# Sensor_Board_0x04_Luminosity_TSL2561_v1.net
KiCad netlist of a schematic drawn in EAGLE
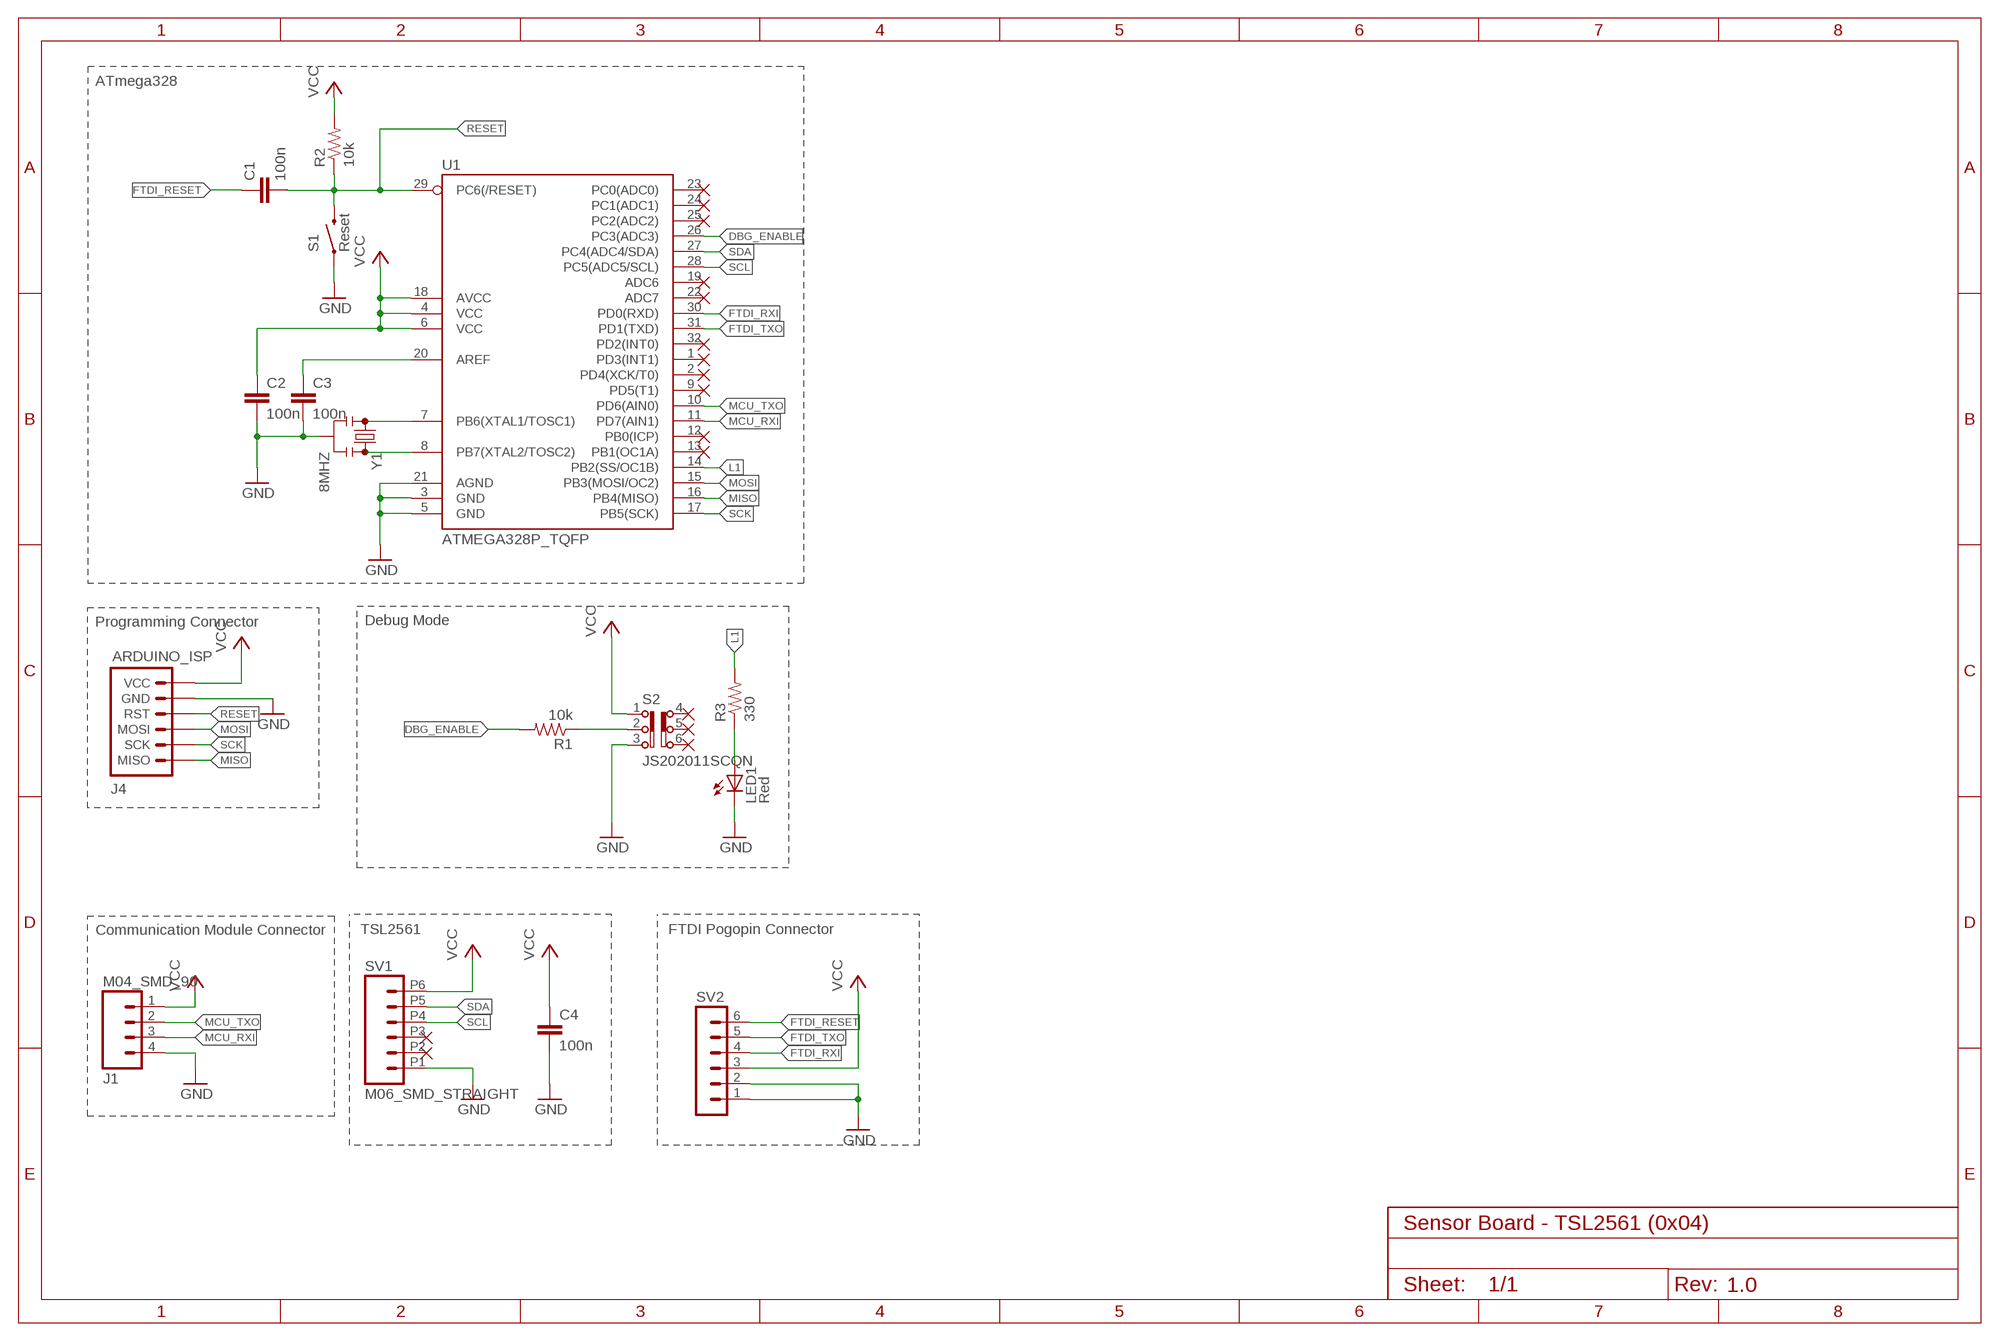
[diagram p0: schematic, sheet 1]

(export (version "E")
  (design (tool "Eeschema 10.0.6"))
  (components
    (comp (ref "C1")
      (value "100n")
      (footprint "eagle-import:C0805")
      (libsource (lib "eagle-import") (part "C"))
    )
    (comp (ref "C2")
      (value "100n")
      (footprint "eagle-import:C0805")
      (libsource (lib "eagle-import") (part "C"))
    )
    (comp (ref "C3")
      (value "100n")
      (footprint "eagle-import:C0805")
      (libsource (lib "eagle-import") (part "C"))
    )
    (comp (ref "C4")
      (value "100n")
      (footprint "eagle-import:C0805")
      (libsource (lib "eagle-import") (part "C"))
    )
    (comp (ref "J1")
      (value "M04_SMD_90")
      (footprint "eagle-import:M04_SMD_90")
      (libsource (lib "eagle-import") (part "M04_SMD_90"))
    )
    (comp (ref "J4")
      (value "ARDUINO_ISP")
      (footprint "eagle-import:M-2X3")
      (libsource (lib "eagle-import") (part "ARDUINO_ISP"))
    )
    (comp (ref "LED1")
      (value "Red")
      (footprint "eagle-import:SML0805")
      (libsource (lib "eagle-import") (part "LEDSML0805"))
    )
    (comp (ref "R1")
      (value "10k")
      (footprint "eagle-import:0805")
      (libsource (lib "eagle-import") (part "RESISTOR0805-RES"))
    )
    (comp (ref "R2")
      (value "10k")
      (footprint "eagle-import:0805")
      (libsource (lib "eagle-import") (part "RESISTOR0805-RES"))
    )
    (comp (ref "R3")
      (value "330")
      (footprint "eagle-import:0805")
      (libsource (lib "eagle-import") (part "RESISTOR0805-RES"))
    )
    (comp (ref "S1")
      (value "Reset")
      (footprint "eagle-import:M-PUSHBUTTON-SMD")
      (libsource (lib "eagle-import") (part "PUSHBUTTON"))
    )
    (comp (ref "S2")
      (value "JS202011SCQN")
      (footprint "eagle-import:JS202011SCQN")
      (libsource (lib "eagle-import") (part "JS202011SCQN"))
    )
    (comp (ref "SV1")
      (value "M06_SMD_STRAIGHT")
      (footprint "eagle-import:M06_SMD_STRAIGHT")
      (libsource (lib "eagle-import") (part "M06_SMD_STRAIGHT"))
    )
    (comp (ref "SV2")
      (value "MA06-1")
      (footprint "eagle-import:MA06-1")
      (libsource (lib "eagle-import") (part "MA06-1"))
    )
    (comp (ref "U1")
      (value "ATMEGA328P_TQFP")
      (footprint "eagle-import:TQFP32-08")
      (libsource (lib "eagle-import") (part "ATMEGA328P_TQFP"))
    )
    (comp (ref "Y1")
      (value "8MHZ")
      (footprint "eagle-import:RESONATOR-SMD")
      (libsource (lib "eagle-import") (part "RESONATOR8MHZ"))
    )
  )
  (nets
    (net (code "1") (name "DBG_ENABLE") (class "Default")
      (node (ref "R1") (pin "2") (pinfunction "2_2") (pintype "passive"))
      (node (ref "U1") (pin "26") (pinfunction "PC3(ADC3)_26") (pintype "bidirectional"))
    )
    (net (code "2") (name "FTDI_RESET") (class "Default")
      (node (ref "C1") (pin "1") (pinfunction "1_1") (pintype "passive"))
      (node (ref "SV2") (pin "6") (pinfunction "6_6") (pintype "passive"))
    )
    (net (code "3") (name "FTDI_RXI") (class "Default")
      (node (ref "SV2") (pin "4") (pinfunction "4_4") (pintype "passive"))
      (node (ref "U1") (pin "30") (pinfunction "PD0(RXD)_30") (pintype "bidirectional"))
    )
    (net (code "4") (name "FTDI_TXO") (class "Default")
      (node (ref "SV2") (pin "5") (pinfunction "5_5") (pintype "passive"))
      (node (ref "U1") (pin "31") (pinfunction "PD1(TXD)_31") (pintype "bidirectional"))
    )
    (net (code "5") (name "GND") (class "Default")
      (node (ref "C2") (pin "2") (pinfunction "2_2") (pintype "passive"))
      (node (ref "C3") (pin "2") (pinfunction "2_2") (pintype "passive"))
      (node (ref "C4") (pin "2") (pinfunction "2_2") (pintype "passive"))
      (node (ref "J1") (pin "4") (pinfunction "4_4") (pintype "passive"))
      (node (ref "J4") (pin "P$5") (pinfunction "GND_P$5") (pintype "passive"))
      (node (ref "LED1") (pin "C") (pinfunction "C_C") (pintype "passive"))
      (node (ref "S1") (pin "1") (pinfunction "LEFT_1") (pintype "passive"))
      (node (ref "S1") (pin "2") (pinfunction "LEFT_2") (pintype "passive"))
      (node (ref "S2") (pin "3") (pinfunction "3_3") (pintype "passive"))
      (node (ref "SV1") (pin "P1") (pinfunction "1_P1") (pintype "passive"))
      (node (ref "SV2") (pin "1") (pinfunction "1_1") (pintype "passive"))
      (node (ref "SV2") (pin "2") (pinfunction "2_2") (pintype "passive"))
      (node (ref "U1") (pin "21") (pinfunction "AGND_21") (pintype "bidirectional"))
      (node (ref "U1") (pin "3") (pinfunction "GND_3") (pintype "bidirectional"))
      (node (ref "U1") (pin "5") (pinfunction "GND_5") (pintype "bidirectional"))
      (node (ref "Y1") (pin "2") (pinfunction "2_2") (pintype "passive"))
    )
    (net (code "6") (name "L1") (class "Default")
      (node (ref "R3") (pin "2") (pinfunction "2_2") (pintype "passive"))
      (node (ref "U1") (pin "14") (pinfunction "PB2(SS/OC1B)_14") (pintype "bidirectional"))
    )
    (net (code "7") (name "MCU_RXI") (class "Default")
      (node (ref "J1") (pin "3") (pinfunction "3_3") (pintype "passive"))
      (node (ref "U1") (pin "11") (pinfunction "PD7(AIN1)_11") (pintype "bidirectional"))
    )
    (net (code "8") (name "MCU_TXO") (class "Default")
      (node (ref "J1") (pin "2") (pinfunction "2_2") (pintype "passive"))
      (node (ref "U1") (pin "10") (pinfunction "PD6(AIN0)_10") (pintype "bidirectional"))
    )
    (net (code "9") (name "MISO") (class "Default")
      (node (ref "J4") (pin "P$1") (pinfunction "MISO_P$1") (pintype "passive"))
      (node (ref "U1") (pin "16") (pinfunction "PB4(MISO)_16") (pintype "bidirectional"))
    )
    (net (code "10") (name "MOSI") (class "Default")
      (node (ref "J4") (pin "P$3") (pinfunction "MOSI_P$3") (pintype "passive"))
      (node (ref "U1") (pin "15") (pinfunction "PB3(MOSI/OC2)_15") (pintype "bidirectional"))
    )
    (net (code "11") (name "Net-(LED1-PadA)") (class "Default")
      (node (ref "LED1") (pin "A") (pinfunction "A_A") (pintype "passive"))
      (node (ref "R3") (pin "1") (pinfunction "1_1") (pintype "passive"))
    )
    (net (code "12") (name "Net-(R1-Pad1)") (class "Default")
      (node (ref "R1") (pin "1") (pinfunction "1_1") (pintype "passive"))
      (node (ref "S2") (pin "2") (pinfunction "2_2") (pintype "passive"))
    )
    (net (code "13") (name "Net-(U1-AREF)") (class "Default")
      (node (ref "C3") (pin "1") (pinfunction "1_1") (pintype "passive"))
      (node (ref "U1") (pin "20") (pinfunction "AREF_20") (pintype "bidirectional"))
    )
    (net (code "14") (name "Net-(U1-PB6(XTAL1{slash}TOSC1))") (class "Default")
      (node (ref "U1") (pin "7") (pinfunction "PB6(XTAL1/TOSC1)_7") (pintype "bidirectional"))
      (node (ref "Y1") (pin "1") (pinfunction "1_1") (pintype "passive"))
    )
    (net (code "15") (name "Net-(U1-PB7(XTAL2{slash}TOSC2))") (class "Default")
      (node (ref "U1") (pin "8") (pinfunction "PB7(XTAL2/TOSC2)_8") (pintype "bidirectional"))
      (node (ref "Y1") (pin "3") (pinfunction "3_3") (pintype "passive"))
    )
    (net (code "16") (name "RESET") (class "Default")
      (node (ref "C1") (pin "2") (pinfunction "2_2") (pintype "passive"))
      (node (ref "J4") (pin "P$4") (pinfunction "RST_P$4") (pintype "passive"))
      (node (ref "R2") (pin "1") (pinfunction "1_1") (pintype "passive"))
      (node (ref "S1") (pin "3") (pinfunction "RIGHT_3") (pintype "passive"))
      (node (ref "S1") (pin "4") (pinfunction "RIGHT_4") (pintype "passive"))
      (node (ref "U1") (pin "29") (pinfunction "PC6(/RESET)_29") (pintype "bidirectional"))
    )
    (net (code "17") (name "SCK") (class "Default")
      (node (ref "J4") (pin "P$2") (pinfunction "SCK_P$2") (pintype "passive"))
      (node (ref "U1") (pin "17") (pinfunction "PB5(SCK)_17") (pintype "bidirectional"))
    )
    (net (code "18") (name "SCL") (class "Default")
      (node (ref "SV1") (pin "P4") (pinfunction "4_P4") (pintype "passive"))
      (node (ref "U1") (pin "28") (pinfunction "PC5(ADC5/SCL)_28") (pintype "bidirectional"))
    )
    (net (code "19") (name "SDA") (class "Default")
      (node (ref "SV1") (pin "P5") (pinfunction "5_P5") (pintype "passive"))
      (node (ref "U1") (pin "27") (pinfunction "PC4(ADC4/SDA)_27") (pintype "bidirectional"))
    )
    (net (code "20") (name "VCC") (class "Default")
      (node (ref "C2") (pin "1") (pinfunction "1_1") (pintype "passive"))
      (node (ref "C4") (pin "1") (pinfunction "1_1") (pintype "passive"))
      (node (ref "J1") (pin "1") (pinfunction "1_1") (pintype "passive"))
      (node (ref "J4") (pin "P$6") (pinfunction "VCC_P$6") (pintype "passive"))
      (node (ref "R2") (pin "2") (pinfunction "2_2") (pintype "passive"))
      (node (ref "S2") (pin "1") (pinfunction "1_1") (pintype "passive"))
      (node (ref "SV1") (pin "P6") (pinfunction "6_P6") (pintype "passive"))
      (node (ref "SV2") (pin "3") (pinfunction "3_3") (pintype "passive"))
      (node (ref "U1") (pin "18") (pinfunction "AVCC_18") (pintype "bidirectional"))
      (node (ref "U1") (pin "4") (pinfunction "VCC_4") (pintype "bidirectional"))
      (node (ref "U1") (pin "6") (pinfunction "VCC_6") (pintype "bidirectional"))
    )
    (net (code "21") (name "unconnected-(S2-Pad4)") (class "Default")
      (node (ref "S2") (pin "4") (pinfunction "4_4") (pintype "passive"))
    )
    (net (code "22") (name "unconnected-(S2-Pad5)") (class "Default")
      (node (ref "S2") (pin "5") (pinfunction "5_5") (pintype "passive"))
    )
    (net (code "23") (name "unconnected-(S2-Pad6)") (class "Default")
      (node (ref "S2") (pin "6") (pinfunction "6_6") (pintype "passive"))
    )
    (net (code "24") (name "unconnected-(SV1-2-PadP2)") (class "Default")
      (node (ref "SV1") (pin "P2") (pinfunction "2_P2") (pintype "passive"))
    )
    (net (code "25") (name "unconnected-(SV1-3-PadP3)") (class "Default")
      (node (ref "SV1") (pin "P3") (pinfunction "3_P3") (pintype "passive"))
    )
    (net (code "26") (name "unconnected-(U1-ADC6-Pad19)") (class "Default")
      (node (ref "U1") (pin "19") (pinfunction "ADC6_19") (pintype "bidirectional"))
    )
    (net (code "27") (name "unconnected-(U1-ADC7-Pad22)") (class "Default")
      (node (ref "U1") (pin "22") (pinfunction "ADC7_22") (pintype "bidirectional"))
    )
    (net (code "28") (name "unconnected-(U1-PB0(ICP)-Pad12)") (class "Default")
      (node (ref "U1") (pin "12") (pinfunction "PB0(ICP)_12") (pintype "bidirectional"))
    )
    (net (code "29") (name "unconnected-(U1-PB1(OC1A)-Pad13)") (class "Default")
      (node (ref "U1") (pin "13") (pinfunction "PB1(OC1A)_13") (pintype "bidirectional"))
    )
    (net (code "30") (name "unconnected-(U1-PC0(ADC0)-Pad23)") (class "Default")
      (node (ref "U1") (pin "23") (pinfunction "PC0(ADC0)_23") (pintype "bidirectional"))
    )
    (net (code "31") (name "unconnected-(U1-PC1(ADC1)-Pad24)") (class "Default")
      (node (ref "U1") (pin "24") (pinfunction "PC1(ADC1)_24") (pintype "bidirectional"))
    )
    (net (code "32") (name "unconnected-(U1-PC2(ADC2)-Pad25)") (class "Default")
      (node (ref "U1") (pin "25") (pinfunction "PC2(ADC2)_25") (pintype "bidirectional"))
    )
    (net (code "33") (name "unconnected-(U1-PD2(INT0)-Pad32)") (class "Default")
      (node (ref "U1") (pin "32") (pinfunction "PD2(INT0)_32") (pintype "bidirectional"))
    )
    (net (code "34") (name "unconnected-(U1-PD3(INT1)-Pad1)") (class "Default")
      (node (ref "U1") (pin "1") (pinfunction "PD3(INT1)_1") (pintype "bidirectional"))
    )
    (net (code "35") (name "unconnected-(U1-PD4(XCK{slash}T0)-Pad2)") (class "Default")
      (node (ref "U1") (pin "2") (pinfunction "PD4(XCK/T0)_2") (pintype "bidirectional"))
    )
    (net (code "36") (name "unconnected-(U1-PD5(T1)-Pad9)") (class "Default")
      (node (ref "U1") (pin "9") (pinfunction "PD5(T1)_9") (pintype "bidirectional"))
    )
  )
)
